# F407.net
KiCad netlist of a schematic drawn in Altium Designer
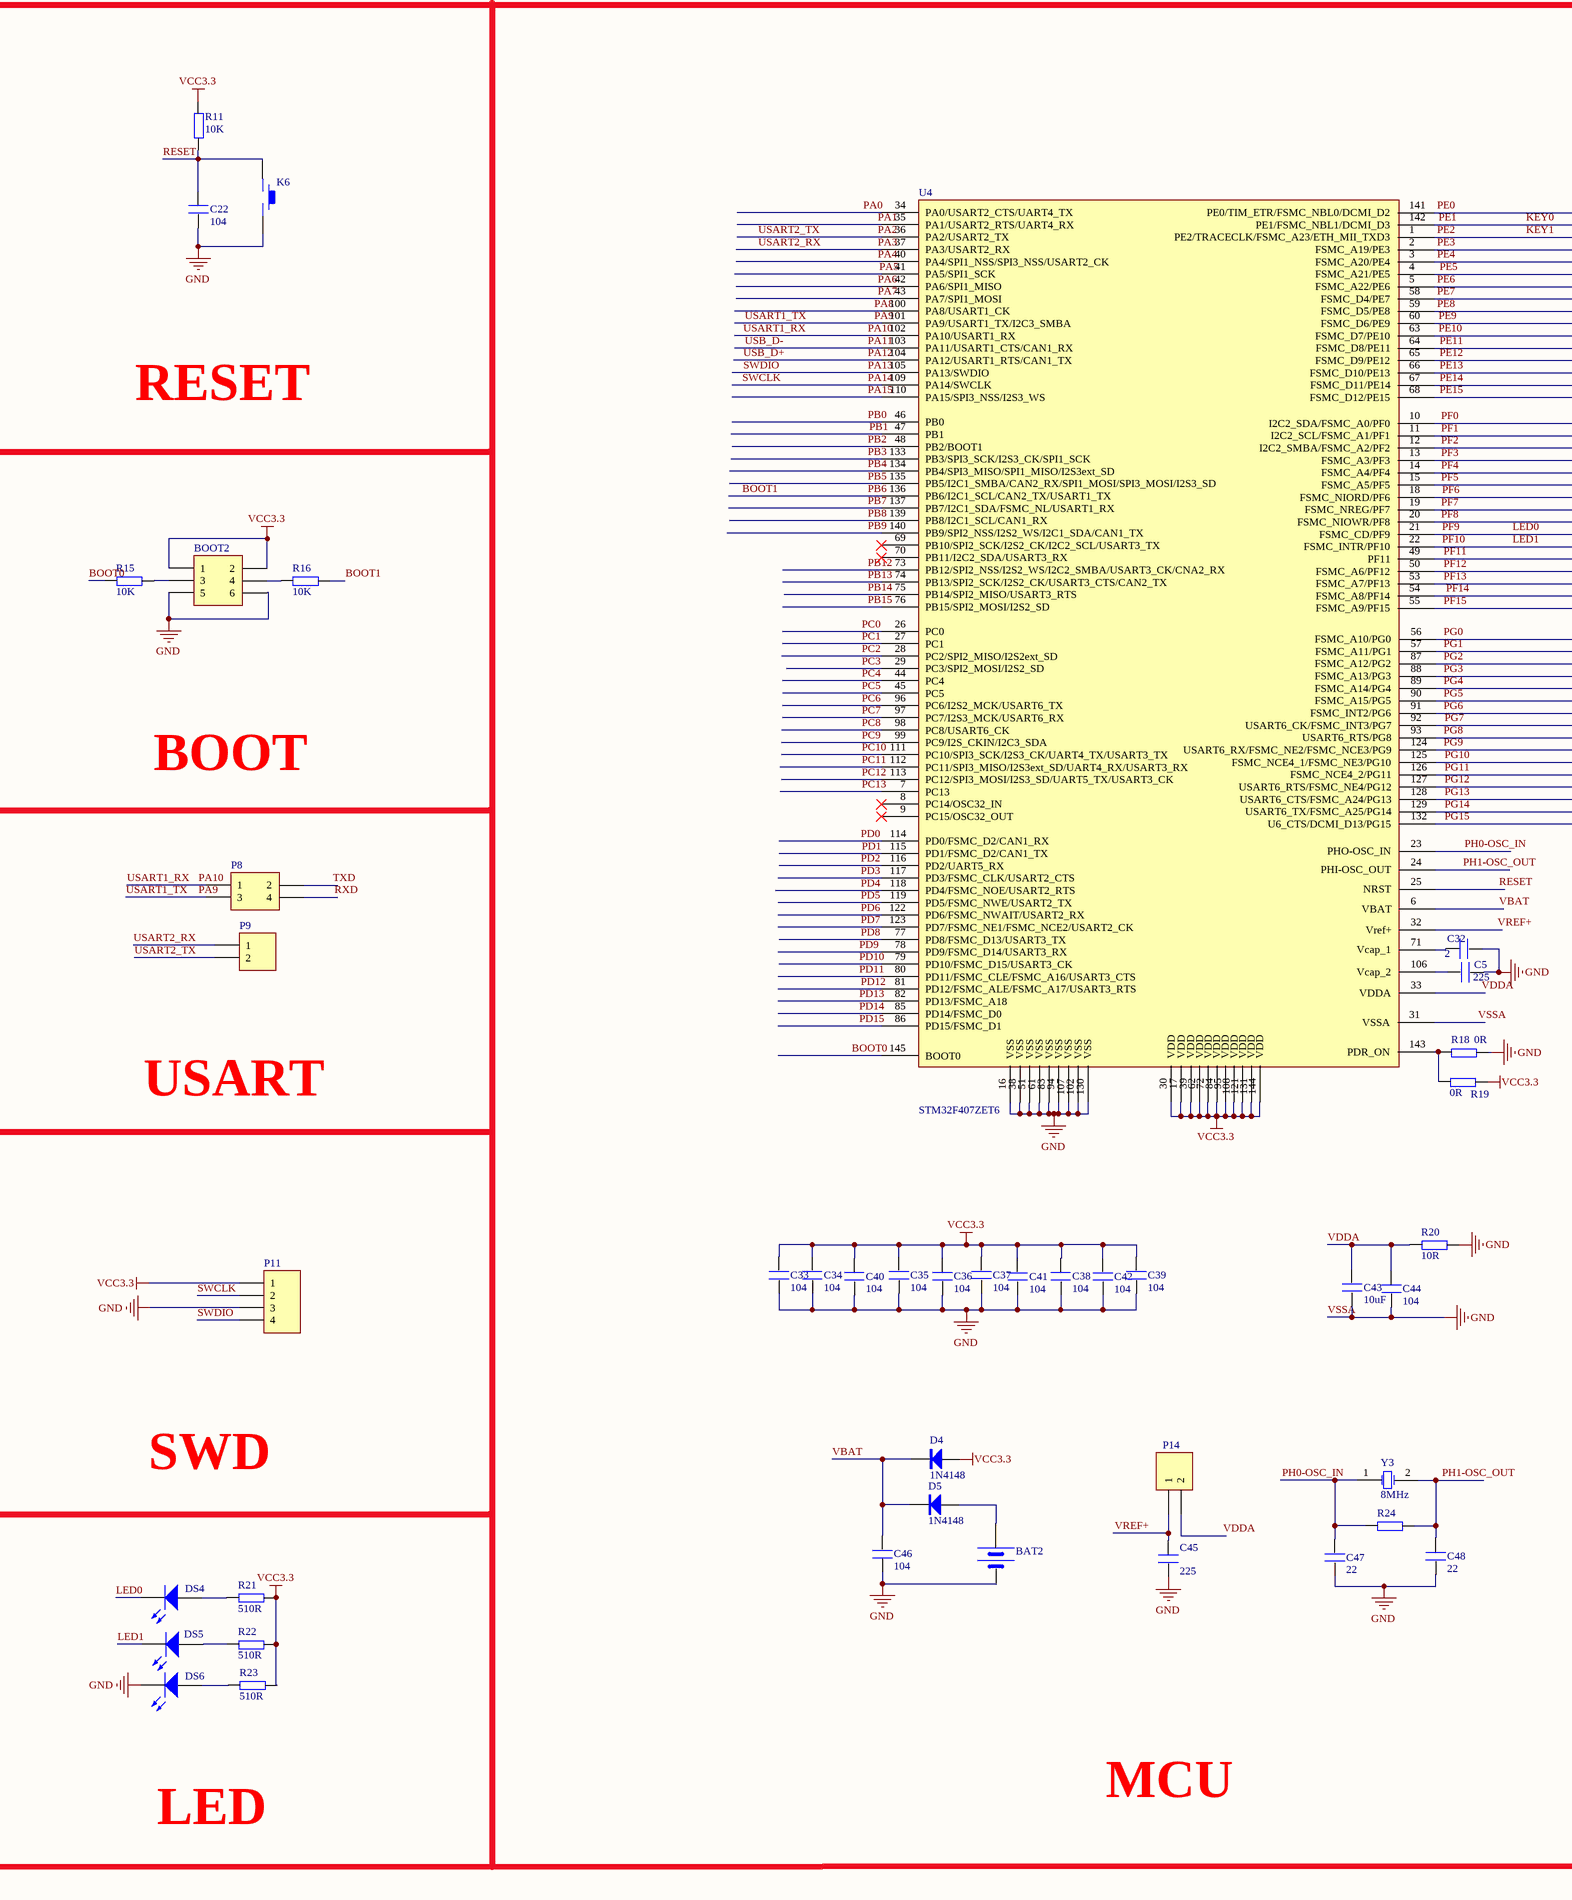
[diagram p0: F407.SchDoc, left]
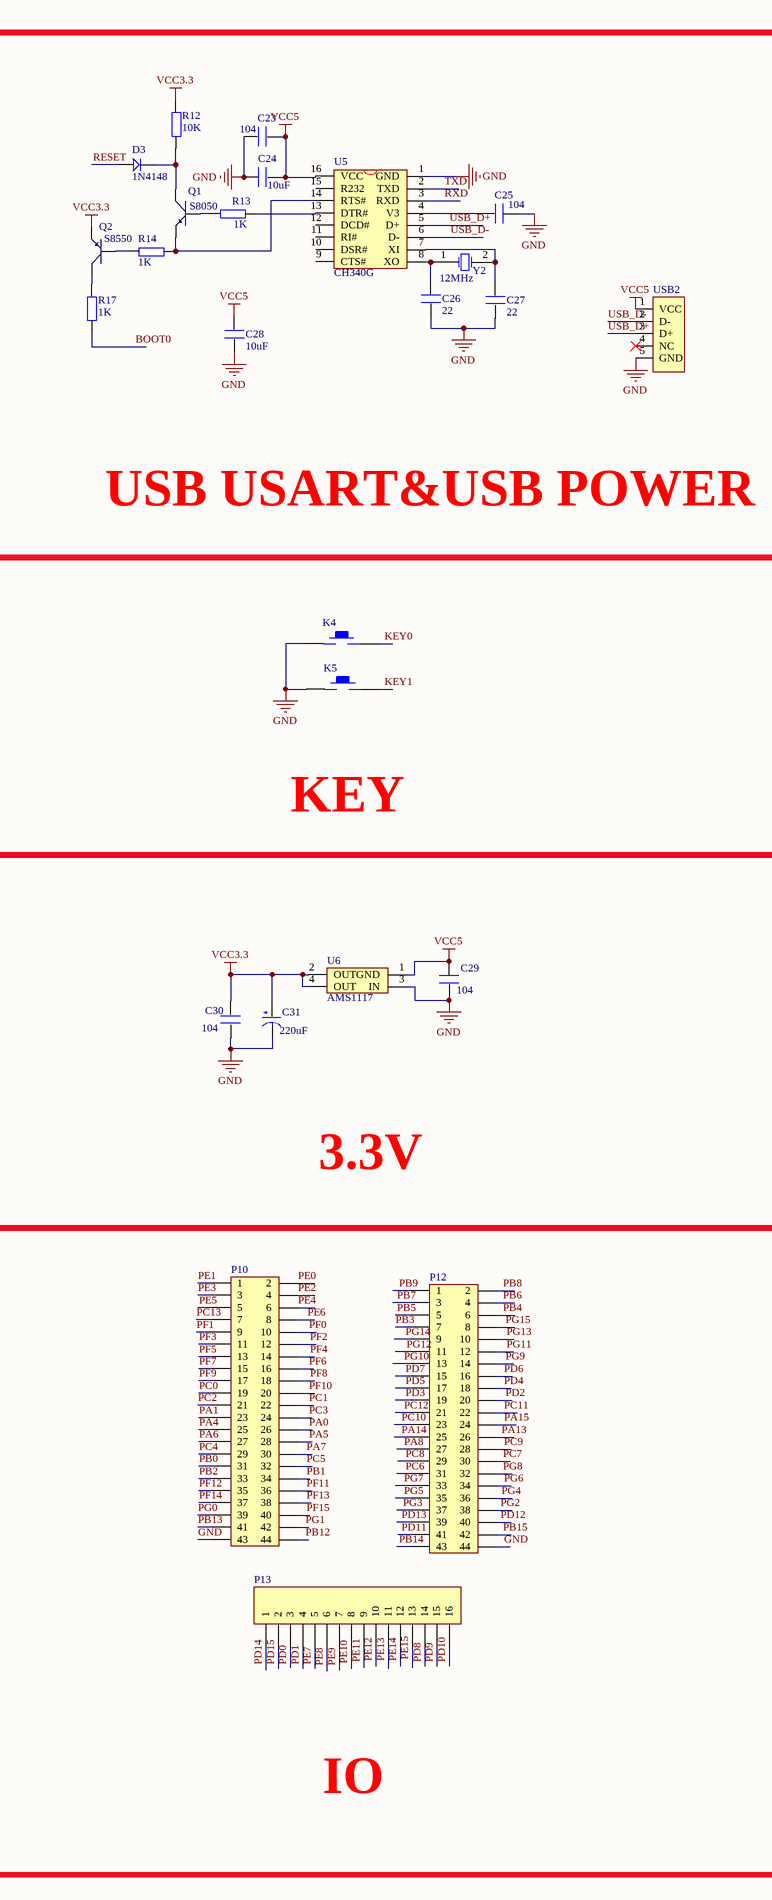
[diagram p1: F407.SchDoc, right]

(export (version "E")
  (design (tool "Eeschema 10.0.6"))
  (components
    (comp (ref "2")
      (value "225")
      (footprint "0603P")
      (libsource (lib "Explorer STM32F407封装库_SCH") (part "C"))
    )
    (comp (ref "BAT2")
      (value "BAT")
      (footprint "BATM")
      (libsource (lib "Explorer STM32F407封装库_SCH") (part "BAT"))
    )
    (comp (ref "BOOT2")
      (value "Header 3X2")
      (footprint "HDR2X3")
      (description "Header, 3-Pin, Dual row")
      (fields (field (name "PUBLISHER") "*"))
      (libsource (lib "Explorer STM32F407封装库_SCH") (part "Header 3X2"))
    )
    (comp (ref "C22")
      (value "104")
      (footprint "0603P")
      (libsource (lib "Explorer STM32F407封装库_SCH") (part "C"))
    )
    (comp (ref "C23")
      (value "104")
      (footprint "0603P")
      (libsource (lib "Explorer STM32F407封装库_SCH") (part "C"))
    )
    (comp (ref "C24")
      (value "10uF")
      (footprint "0603P")
      (libsource (lib "Explorer STM32F407封装库_SCH") (part "C"))
    )
    (comp (ref "C25")
      (value "104")
      (footprint "0603P")
      (libsource (lib "Explorer STM32F407封装库_SCH") (part "C"))
    )
    (comp (ref "C26")
      (value "22")
      (footprint "0603P")
      (libsource (lib "Explorer STM32F407封装库_SCH") (part "C"))
    )
    (comp (ref "C27")
      (value "22")
      (footprint "0603P")
      (libsource (lib "Explorer STM32F407封装库_SCH") (part "C"))
    )
    (comp (ref "C28")
      (value "10uF")
      (footprint "0603P")
      (libsource (lib "Explorer STM32F407封装库_SCH") (part "C"))
    )
    (comp (ref "C29")
      (value "104")
      (footprint "0603P")
      (libsource (lib "Explorer STM32F407封装库_SCH") (part "C"))
    )
    (comp (ref "C30")
      (value "104")
      (footprint "0603P")
      (libsource (lib "Explorer STM32F407封装库_SCH") (part "C"))
    )
    (comp (ref "C31")
      (value "220uF")
      (footprint "C1206")
      (libsource (lib "Explorer STM32F407封装库_SCH") (part "CAP"))
    )
    (comp (ref "C32")
      (value "C5")
      (footprint "0603P")
      (libsource (lib "Explorer STM32F407封装库_SCH") (part "C"))
    )
    (comp (ref "C33")
      (value "104")
      (footprint "0603P")
      (libsource (lib "Explorer STM32F407封装库_SCH") (part "C"))
    )
    (comp (ref "C34")
      (value "104")
      (footprint "0603P")
      (libsource (lib "Explorer STM32F407封装库_SCH") (part "C"))
    )
    (comp (ref "C35")
      (value "104")
      (footprint "0603P")
      (libsource (lib "Explorer STM32F407封装库_SCH") (part "C"))
    )
    (comp (ref "C36")
      (value "104")
      (footprint "0603P")
      (libsource (lib "Explorer STM32F407封装库_SCH") (part "C"))
    )
    (comp (ref "C37")
      (value "104")
      (footprint "0603P")
      (libsource (lib "Explorer STM32F407封装库_SCH") (part "C"))
    )
    (comp (ref "C38")
      (value "104")
      (footprint "0603P")
      (libsource (lib "Explorer STM32F407封装库_SCH") (part "C"))
    )
    (comp (ref "C39")
      (value "104")
      (footprint "0603P")
      (libsource (lib "Explorer STM32F407封装库_SCH") (part "C"))
    )
    (comp (ref "C40")
      (value "104")
      (footprint "0603P")
      (libsource (lib "Explorer STM32F407封装库_SCH") (part "C"))
    )
    (comp (ref "C41")
      (value "104")
      (footprint "0603P")
      (libsource (lib "Explorer STM32F407封装库_SCH") (part "C"))
    )
    (comp (ref "C42")
      (value "104")
      (footprint "0603P")
      (libsource (lib "Explorer STM32F407封装库_SCH") (part "C"))
    )
    (comp (ref "C43")
      (value "10uF")
      (footprint "0603P")
      (libsource (lib "Explorer STM32F407封装库_SCH") (part "C"))
    )
    (comp (ref "C44")
      (value "104")
      (footprint "0603P")
      (libsource (lib "Explorer STM32F407封装库_SCH") (part "C"))
    )
    (comp (ref "C45")
      (value "225")
      (footprint "0603P")
      (libsource (lib "Explorer STM32F407封装库_SCH") (part "C"))
    )
    (comp (ref "C46")
      (value "104")
      (footprint "0603P")
      (libsource (lib "Explorer STM32F407封装库_SCH") (part "C"))
    )
    (comp (ref "C47")
      (value "22")
      (footprint "0603P")
      (libsource (lib "Explorer STM32F407封装库_SCH") (part "C"))
    )
    (comp (ref "C48")
      (value "22")
      (footprint "0603P")
      (libsource (lib "Explorer STM32F407封装库_SCH") (part "C"))
    )
    (comp (ref "D3")
      (value "1N4148")
      (footprint "SOD-123")
      (libsource (lib "Explorer STM32F407封装库_SCH") (part "D"))
    )
    (comp (ref "D4")
      (value "1N4148")
      (footprint "MINI_MELF (LL34)")
      (description "高速开关二极管")
      (fields (field (name "版权归属") "源创客"))
      (libsource (lib "8.1   - 二极管-整流桥") (part "1N4148"))
    )
    (comp (ref "D5")
      (value "1N4148")
      (footprint "MINI_MELF (LL34)")
      (description "高速开关二极管")
      (fields (field (name "版权归属") "源创客"))
      (libsource (lib "8.1   - 二极管-整流桥") (part "1N4148"))
    )
    (comp (ref "DS4")
      (value "LED0")
      (footprint "SMDLED")
      (description "Typical RED, GREEN, YELLOW, AMBER GaAs LED")
      (fields (field (name "PUBLISHER") "*"))
      (libsource (lib "Explorer STM32F407封装库_SCH") (part "LED2"))
    )
    (comp (ref "DS5")
      (value "LED1")
      (footprint "SMDLED")
      (description "Typical RED, GREEN, YELLOW, AMBER GaAs LED")
      (fields (field (name "PUBLISHER") "*"))
      (libsource (lib "Explorer STM32F407封装库_SCH") (part "LED2"))
    )
    (comp (ref "DS6")
      (value "LED3")
      (footprint "SMDLED")
      (description "Typical RED, GREEN, YELLOW, AMBER GaAs LED")
      (fields (field (name "PUBLISHER") "*"))
      (libsource (lib "Explorer STM32F407封装库_SCH") (part "LED2"))
    )
    (comp (ref "K4")
      (value "KEY_M")
      (footprint "KEY_M")
      (libsource (lib "Explorer STM32F407封装库_SCH") (part "KEY_M"))
    )
    (comp (ref "K5")
      (value "KEY_M")
      (footprint "KEY_M")
      (libsource (lib "Explorer STM32F407封装库_SCH") (part "KEY_M"))
    )
    (comp (ref "K6") (value "~") (footprint "KEY_M") (libsource (lib "") (part "KEY_M_1")))
    (comp (ref "P8")
      (value "Header 2X2")
      (footprint "HDR2X2")
      (description "Header, 2-Pin, Dual row")
      (fields (field (name "PUBLISHER") "*"))
      (libsource (lib "Explorer STM32F407封装库_SCH") (part "Header 2X2"))
    )
    (comp (ref "P9")
      (value "Header 2")
      (footprint "HDR1X2")
      (description "Header, 2-Pin")
      (fields (field (name "PUBLISHER") "*"))
      (libsource (lib "") (part "Header 2_1"))
    )
    (comp (ref "P10")
      (value "HEAD2*22")
      (footprint "HEAD2*22")
      (libsource (lib "Explorer STM32F407封装库_SCH") (part "HEAD2*22"))
    )
    (comp (ref "P11")
      (value "Header 4")
      (footprint "HDR1X4")
      (description "Header, 4-Pin")
      (fields (field (name "PUBLISHER") "*"))
      (libsource (lib "Explorer STM32F407封装库_SCH") (part "Header 4"))
    )
    (comp (ref "P12")
      (value "HEAD2*22")
      (footprint "HEAD2*22")
      (libsource (lib "Explorer STM32F407封装库_SCH") (part "HEAD2*22"))
    )
    (comp (ref "P13")
      (value "Header 16")
      (footprint "HDR1X16")
      (description "Header, 16-Pin")
      (fields (field (name "PUBLISHER") "*"))
      (libsource (lib "Explorer STM32F407封装库_SCH") (part "Header 16"))
    )
    (comp (ref "P14")
      (value "~")
      (footprint "HDR1X2")
      (description "Header, 2-Pin")
      (fields (field (name "PUBLISHER") "*"))
      (libsource (lib "Explorer STM32F407封装库_SCH") (part "Header 2"))
    )
    (comp (ref "Q1")
      (value "S8050")
      (footprint "SOT-23R")
      (description "8050/BCW846/BCW847")
      (libsource (lib "Explorer STM32F407封装库_SCH") (part "NPN"))
    )
    (comp (ref "Q2")
      (value "S8550")
      (footprint "SOT-23R")
      (description "8550/BCW68")
      (libsource (lib "Explorer STM32F407封装库_SCH") (part "PNP"))
    )
    (comp (ref "R11")
      (value "10K")
      (footprint "0805")
      (libsource (lib "Explorer STM32F407封装库_SCH") (part "R"))
    )
    (comp (ref "R12")
      (value "10K")
      (footprint "0805")
      (libsource (lib "Explorer STM32F407封装库_SCH") (part "R"))
    )
    (comp (ref "R13")
      (value "1K")
      (footprint "0805")
      (libsource (lib "Explorer STM32F407封装库_SCH") (part "R"))
    )
    (comp (ref "R14")
      (value "1K")
      (footprint "0805")
      (libsource (lib "Explorer STM32F407封装库_SCH") (part "R"))
    )
    (comp (ref "R15")
      (value "10K")
      (footprint "0805")
      (libsource (lib "Explorer STM32F407封装库_SCH") (part "R"))
    )
    (comp (ref "R16")
      (value "10K")
      (footprint "0805")
      (libsource (lib "Explorer STM32F407封装库_SCH") (part "R"))
    )
    (comp (ref "R17")
      (value "1K")
      (footprint "0805")
      (libsource (lib "Explorer STM32F407封装库_SCH") (part "R"))
    )
    (comp (ref "R18")
      (value "0R")
      (footprint "0805")
      (libsource (lib "Explorer STM32F407封装库_SCH") (part "R"))
    )
    (comp (ref "R19")
      (value "0R")
      (footprint "0805")
      (libsource (lib "Explorer STM32F407封装库_SCH") (part "R"))
    )
    (comp (ref "R20")
      (value "10R")
      (footprint "0805")
      (libsource (lib "Explorer STM32F407封装库_SCH") (part "R"))
    )
    (comp (ref "R21")
      (value "510R")
      (footprint "0805")
      (libsource (lib "Explorer STM32F407封装库_SCH") (part "R"))
    )
    (comp (ref "R22")
      (value "510R")
      (footprint "0805")
      (libsource (lib "Explorer STM32F407封装库_SCH") (part "R"))
    )
    (comp (ref "R23")
      (value "510R")
      (footprint "0805")
      (libsource (lib "Explorer STM32F407封装库_SCH") (part "R"))
    )
    (comp (ref "R24") (value "R") (footprint "0805") (libsource (lib "Explorer STM32F407封装库_SCH") (part "R")))
    (comp (ref "U4")
      (value "STM32F407ZET6")
      (footprint "LQFP144")
      (libsource (lib "PCB_Project") (part "STM32F407ZET6"))
    )
    (comp (ref "U5")
      (value "CH340G")
      (footprint "SOP16M")
      (description "USB2UART")
      (libsource (lib "Explorer STM32F407封装库_SCH") (part "CH340G"))
    )
    (comp (ref "U6")
      (value "AMS1117")
      (footprint "AMS1117")
      (libsource (lib "Explorer STM32F407封装库_SCH") (part "AMS1117"))
    )
    (comp (ref "USB2")
      (value "USB5")
      (footprint "USB/SM0.8-6H5")
      (libsource (lib "Explorer STM32F407封装库_SCH") (part "USB5"))
    )
    (comp (ref "Y2")
      (value "12MHz")
      (footprint "XTAL_US")
      (description "Crystal Oscillator")
      (fields (field (name "PUBLISHER") "*"))
      (libsource (lib "Explorer STM32F407封装库_SCH") (part "XTAL"))
    )
    (comp (ref "Y3")
      (value "8MHz")
      (footprint "XTAL_US")
      (description "Crystal Oscillator")
      (fields (field (name "PUBLISHER") "*"))
      (libsource (lib "Explorer STM32F407封装库_SCH") (part "XTAL"))
    )
  )
  (nets
    (net (code "1") (name "/BOOT0") (class "Default")
      (node (ref "R15") (pin "1") (pintype "passive"))
      (node (ref "R17") (pin "1") (pintype "passive"))
      (node (ref "U4") (pin "145") (pinfunction "BOOT0_145") (pintype "passive"))
    )
    (net (code "2") (name "/BOOT1") (class "Default")
      (node (ref "P12") (pin "4") (pinfunction "4_4") (pintype "passive"))
      (node (ref "R16") (pin "2") (pintype "passive"))
      (node (ref "U4") (pin "136") (pinfunction "PB6/I2C1_SCL/CAN2_TX/USART1_TX_136") (pintype "passive"))
    )
    (net (code "3") (name "/KEY0") (class "Default")
      (node (ref "K4") (pin "2") (pinfunction "2_2") (pintype "passive"))
      (node (ref "P10") (pin "1") (pinfunction "1_1") (pintype "passive"))
      (node (ref "U4") (pin "142") (pinfunction "PE1/FSMC_NBL1/DCMI_D3_142") (pintype "passive"))
    )
    (net (code "4") (name "/KEY1") (class "Default")
      (node (ref "K5") (pin "2") (pinfunction "2_2") (pintype "passive"))
      (node (ref "P10") (pin "4") (pinfunction "4_4") (pintype "passive"))
      (node (ref "U4") (pin "1") (pinfunction "PE2/TRACECLK/FSMC_A23/ETH_MII_TXD3_1") (pintype "passive"))
    )
    (net (code "5") (name "/LED0") (class "Default")
      (node (ref "DS4") (pin "2") (pinfunction "K_2") (pintype "passive"))
      (node (ref "P10") (pin "17") (pinfunction "17_17") (pintype "passive"))
      (node (ref "U4") (pin "21") (pinfunction "FSMC_CD/PF9_21") (pintype "passive"))
    )
    (net (code "6") (name "/LED1") (class "Default")
      (node (ref "DS5") (pin "2") (pinfunction "K_2") (pintype "passive"))
      (node (ref "P10") (pin "20") (pinfunction "20_20") (pintype "passive"))
      (node (ref "U4") (pin "22") (pinfunction "FSMC_INTR/PF10_22") (pintype "passive"))
    )
    (net (code "7") (name "/PA0") (class "Default")
      (node (ref "P10") (pin "26") (pinfunction "26_26") (pintype "passive"))
      (node (ref "U4") (pin "34") (pinfunction "PA0/USART2_CTS/UART4_TX_34") (pintype "passive"))
    )
    (net (code "8") (name "/PA1") (class "Default")
      (node (ref "P10") (pin "23") (pinfunction "23_23") (pintype "passive"))
      (node (ref "U4") (pin "35") (pinfunction "PA1/USART2_RTS/UART4_RX_35") (pintype "passive"))
    )
    (net (code "9") (name "/PA2") (class "Default")
      (node (ref "P9") (pin "2") (pinfunction "2_2") (pintype "passive"))
      (node (ref "U4") (pin "36") (pinfunction "PA2/USART2_TX_36") (pintype "passive"))
    )
    (net (code "10") (name "/PA3") (class "Default")
      (node (ref "P9") (pin "1") (pinfunction "1_1") (pintype "passive"))
      (node (ref "U4") (pin "37") (pinfunction "PA3/USART2_RX_37") (pintype "passive"))
    )
    (net (code "11") (name "/PA4") (class "Default")
      (node (ref "P10") (pin "25") (pinfunction "25_25") (pintype "passive"))
      (node (ref "U4") (pin "40") (pinfunction "PA4/SPI1_NSS/SPI3_NSS/USART2_CK_40") (pintype "passive"))
    )
    (net (code "12") (name "/PA5") (class "Default")
      (node (ref "P10") (pin "28") (pinfunction "28_28") (pintype "passive"))
      (node (ref "U4") (pin "41") (pinfunction "PA5/SPI1_SCK_41") (pintype "passive"))
    )
    (net (code "13") (name "/PA6") (class "Default")
      (node (ref "P10") (pin "27") (pinfunction "27_27") (pintype "passive"))
      (node (ref "U4") (pin "42") (pinfunction "PA6/SPI1_MISO_42") (pintype "passive"))
    )
    (net (code "14") (name "/PA7") (class "Default")
      (node (ref "P10") (pin "30") (pinfunction "30_30") (pintype "passive"))
      (node (ref "U4") (pin "43") (pinfunction "PA7/SPI1_MOSI_43") (pintype "passive"))
    )
    (net (code "15") (name "/PA8") (class "Default")
      (node (ref "P12") (pin "27") (pinfunction "27_27") (pintype "passive"))
      (node (ref "U4") (pin "100") (pinfunction "PA8/USART1_CK_100") (pintype "passive"))
    )
    (net (code "16") (name "/PA9") (class "Default")
      (node (ref "P8") (pin "3") (pinfunction "3_3") (pintype "passive"))
      (node (ref "U4") (pin "101") (pinfunction "PA9/USART1_TX/I2C3_SMBA_101") (pintype "passive"))
    )
    (net (code "17") (name "/PA10") (class "Default")
      (node (ref "P8") (pin "1") (pinfunction "1_1") (pintype "passive"))
      (node (ref "U4") (pin "102") (pinfunction "PA10/USART1_RX_102") (pintype "passive"))
    )
    (net (code "18") (name "/PA11") (class "Default")
      (node (ref "U4") (pin "103") (pinfunction "PA11/USART1_CTS/CAN1_RX_103") (pintype "passive"))
      (node (ref "U5") (pin "6") (pinfunction "D-_6") (pintype "passive"))
      (node (ref "USB2") (pin "2") (pinfunction "D-_2") (pintype "passive"))
    )
    (net (code "19") (name "/PA12") (class "Default")
      (node (ref "U4") (pin "104") (pinfunction "PA12/USART1_RTS/CAN1_TX_104") (pintype "passive"))
      (node (ref "U5") (pin "5") (pinfunction "D+_5") (pintype "passive"))
      (node (ref "USB2") (pin "3") (pinfunction "D+_3") (pintype "passive"))
    )
    (net (code "20") (name "/PA13") (class "Default")
      (node (ref "P11") (pin "4") (pinfunction "4_4") (pintype "passive"))
      (node (ref "P12") (pin "26") (pinfunction "26_26") (pintype "passive"))
      (node (ref "U4") (pin "105") (pinfunction "PA13/SWDIO_105") (pintype "passive"))
    )
    (net (code "21") (name "/PA14") (class "Default")
      (node (ref "P11") (pin "2") (pinfunction "2_2") (pintype "passive"))
      (node (ref "P12") (pin "25") (pinfunction "25_25") (pintype "passive"))
      (node (ref "U4") (pin "109") (pinfunction "PA14/SWCLK_109") (pintype "passive"))
    )
    (net (code "22") (name "/PA15") (class "Default")
      (node (ref "P12") (pin "24") (pinfunction "24_24") (pintype "passive"))
      (node (ref "U4") (pin "110") (pinfunction "PA15/SPI3_NSS/I2S3_WS_110") (pintype "passive"))
    )
    (net (code "23") (name "/PB0") (class "Default")
      (node (ref "P10") (pin "31") (pinfunction "31_31") (pintype "passive"))
      (node (ref "U4") (pin "46") (pinfunction "PB0_46") (pintype "passive"))
    )
    (net (code "24") (name "/PB1") (class "Default")
      (node (ref "P10") (pin "34") (pinfunction "34_34") (pintype "passive"))
      (node (ref "U4") (pin "47") (pinfunction "PB1_47") (pintype "passive"))
    )
    (net (code "25") (name "/PB2") (class "Default")
      (node (ref "P10") (pin "33") (pinfunction "33_33") (pintype "passive"))
      (node (ref "U4") (pin "48") (pinfunction "PB2/BOOT1_48") (pintype "passive"))
    )
    (net (code "26") (name "/PB3") (class "Default")
      (node (ref "P12") (pin "7") (pinfunction "7_7") (pintype "passive"))
      (node (ref "U4") (pin "133") (pinfunction "PB3/SPI3_SCK/I2S3_CK/SPI1_SCK_133") (pintype "passive"))
    )
    (net (code "27") (name "/PB4") (class "Default")
      (node (ref "P12") (pin "6") (pinfunction "6_6") (pintype "passive"))
      (node (ref "U4") (pin "134") (pinfunction "PB4/SPI3_MISO/SPI1_MISO/I2S3ext_SD_134") (pintype "passive"))
    )
    (net (code "28") (name "/PB5") (class "Default")
      (node (ref "P12") (pin "5") (pinfunction "5_5") (pintype "passive"))
      (node (ref "U4") (pin "135") (pinfunction "PB5/I2C1_SMBA/CAN2_RX/SPI1_MOSI/SPI3_MOSI/I2S3_SD_135") (pintype "passive"))
    )
    (net (code "29") (name "/PB7") (class "Default")
      (node (ref "P12") (pin "3") (pinfunction "3_3") (pintype "passive"))
      (node (ref "U4") (pin "137") (pinfunction "PB7/I2C1_SDA/FSMC_NL/USART1_RX_137") (pintype "passive"))
    )
    (net (code "30") (name "/PB8") (class "Default")
      (node (ref "P12") (pin "2") (pinfunction "2_2") (pintype "passive"))
      (node (ref "U4") (pin "139") (pinfunction "PB8/I2C1_SCL/CAN1_RX_139") (pintype "passive"))
    )
    (net (code "31") (name "/PB9") (class "Default")
      (node (ref "P12") (pin "1") (pinfunction "1_1") (pintype "passive"))
      (node (ref "U4") (pin "140") (pinfunction "PB9/SPI2_NSS/I2S2_WS/I2C1_SDA/CAN1_TX_140") (pintype "passive"))
    )
    (net (code "32") (name "/PB12") (class "Default")
      (node (ref "P10") (pin "44") (pinfunction "44_44") (pintype "passive"))
      (node (ref "U4") (pin "73") (pinfunction "PB12/SPI2_NSS/I2S2_WS/I2C2_SMBA/USART3_CK/CNA2_RX_73") (pintype "passive"))
    )
    (net (code "33") (name "/PB13") (class "Default")
      (node (ref "P10") (pin "41") (pinfunction "41_41") (pintype "passive"))
      (node (ref "U4") (pin "74") (pinfunction "PB13/SPI2_SCK/I2S2_CK/USART3_CTS/CAN2_TX_74") (pintype "passive"))
    )
    (net (code "34") (name "/PB14") (class "Default")
      (node (ref "P12") (pin "43") (pinfunction "43_43") (pintype "passive"))
      (node (ref "U4") (pin "75") (pinfunction "PB14/SPI2_MISO/USART3_RTS_75") (pintype "passive"))
    )
    (net (code "35") (name "/PB15") (class "Default")
      (node (ref "P12") (pin "42") (pinfunction "42_42") (pintype "passive"))
      (node (ref "U4") (pin "76") (pinfunction "PB15/SPI2_MOSI/I2S2_SD_76") (pintype "passive"))
    )
    (net (code "36") (name "/PC0") (class "Default")
      (node (ref "P10") (pin "19") (pinfunction "19_19") (pintype "passive"))
      (node (ref "U4") (pin "26") (pinfunction "PC0_26") (pintype "passive"))
    )
    (net (code "37") (name "/PC1") (class "Default")
      (node (ref "P10") (pin "22") (pinfunction "22_22") (pintype "passive"))
      (node (ref "U4") (pin "27") (pinfunction "PC1_27") (pintype "passive"))
    )
    (net (code "38") (name "/PC2") (class "Default")
      (node (ref "P10") (pin "21") (pinfunction "21_21") (pintype "passive"))
      (node (ref "U4") (pin "28") (pinfunction "PC2/SPI2_MISO/I2S2ext_SD_28") (pintype "passive"))
    )
    (net (code "39") (name "/PC3") (class "Default")
      (node (ref "P10") (pin "24") (pinfunction "24_24") (pintype "passive"))
      (node (ref "U4") (pin "29") (pinfunction "PC3/SPI2_MOSI/I2S2_SD_29") (pintype "passive"))
    )
    (net (code "40") (name "/PC4") (class "Default")
      (node (ref "P10") (pin "29") (pinfunction "29_29") (pintype "passive"))
      (node (ref "U4") (pin "44") (pinfunction "PC4_44") (pintype "passive"))
    )
    (net (code "41") (name "/PC5") (class "Default")
      (node (ref "P10") (pin "32") (pinfunction "32_32") (pintype "passive"))
      (node (ref "U4") (pin "45") (pinfunction "PC5_45") (pintype "passive"))
    )
    (net (code "42") (name "/PC6") (class "Default")
      (node (ref "P12") (pin "31") (pinfunction "31_31") (pintype "passive"))
      (node (ref "U4") (pin "96") (pinfunction "PC6/I2S2_MCK/USART6_TX_96") (pintype "passive"))
    )
    (net (code "43") (name "/PC7") (class "Default")
      (node (ref "P12") (pin "30") (pinfunction "30_30") (pintype "passive"))
      (node (ref "U4") (pin "97") (pinfunction "PC7/I2S3_MCK/USART6_RX_97") (pintype "passive"))
    )
    (net (code "44") (name "/PC8") (class "Default")
      (node (ref "P12") (pin "29") (pinfunction "29_29") (pintype "passive"))
      (node (ref "U4") (pin "98") (pinfunction "PC8/USART6_CK_98") (pintype "passive"))
    )
    (net (code "45") (name "/PC9") (class "Default")
      (node (ref "P12") (pin "28") (pinfunction "28_28") (pintype "passive"))
      (node (ref "U4") (pin "99") (pinfunction "PC9/I2S_CKIN/I2C3_SDA_99") (pintype "passive"))
    )
    (net (code "46") (name "/PC10") (class "Default")
      (node (ref "P12") (pin "23") (pinfunction "23_23") (pintype "passive"))
      (node (ref "U4") (pin "111") (pinfunction "PC10/SPI3_SCK/I2S3_CK/UART4_TX/USART3_TX_111") (pintype "passive"))
    )
    (net (code "47") (name "/PC11") (class "Default")
      (node (ref "P12") (pin "22") (pinfunction "22_22") (pintype "passive"))
      (node (ref "U4") (pin "112") (pinfunction "PC11/SPI3_MISO/I2S3ext_SD/UART4_RX/USART3_RX_112") (pintype "passive"))
    )
    (net (code "48") (name "/PC12") (class "Default")
      (node (ref "P12") (pin "21") (pinfunction "21_21") (pintype "passive"))
      (node (ref "U4") (pin "113") (pinfunction "PC12/SPI3_MOSI/I2S3_SD/UART5_TX/USART3_CK_113") (pintype "passive"))
    )
    (net (code "49") (name "/PC13") (class "Default")
      (node (ref "P10") (pin "7") (pinfunction "7_7") (pintype "passive"))
      (node (ref "U4") (pin "7") (pinfunction "PC13_7") (pintype "passive"))
    )
    (net (code "50") (name "/PD0") (class "Default")
      (node (ref "P13") (pin "3") (pinfunction "3_3") (pintype "passive"))
      (node (ref "U4") (pin "114") (pinfunction "PD0/FSMC_D2/CAN1_RX_114") (pintype "passive"))
    )
    (net (code "51") (name "/PD1") (class "Default")
      (node (ref "P13") (pin "4") (pinfunction "4_4") (pintype "passive"))
      (node (ref "U4") (pin "115") (pinfunction "PD1/FSMC_D2/CAN1_TX_115") (pintype "passive"))
    )
    (net (code "52") (name "/PD2") (class "Default")
      (node (ref "P12") (pin "20") (pinfunction "20_20") (pintype "passive"))
      (node (ref "U4") (pin "116") (pinfunction "PD2/UART5_RX_116") (pintype "passive"))
    )
    (net (code "53") (name "/PD3") (class "Default")
      (node (ref "P12") (pin "19") (pinfunction "19_19") (pintype "passive"))
      (node (ref "U4") (pin "117") (pinfunction "PD3/FSMC_CLK/USART2_CTS_117") (pintype "passive"))
    )
    (net (code "54") (name "/PD4") (class "Default")
      (node (ref "P12") (pin "18") (pinfunction "18_18") (pintype "passive"))
      (node (ref "U4") (pin "118") (pinfunction "PD4/FSMC_NOE/USART2_RTS_118") (pintype "passive"))
    )
    (net (code "55") (name "/PD5") (class "Default")
      (node (ref "P12") (pin "17") (pinfunction "17_17") (pintype "passive"))
      (node (ref "U4") (pin "119") (pinfunction "PD5/FSMC_NWE/USART2_TX_119") (pintype "passive"))
    )
    (net (code "56") (name "/PD6") (class "Default")
      (node (ref "P12") (pin "16") (pinfunction "16_16") (pintype "passive"))
      (node (ref "U4") (pin "122") (pinfunction "PD6/FSMC_NWAIT/USART2_RX_122") (pintype "passive"))
    )
    (net (code "57") (name "/PD7") (class "Default")
      (node (ref "P12") (pin "15") (pinfunction "15_15") (pintype "passive"))
      (node (ref "U4") (pin "123") (pinfunction "PD7/FSMC_NE1/FSMC_NCE2/USART2_CK_123") (pintype "passive"))
    )
    (net (code "58") (name "/PD8") (class "Default")
      (node (ref "P13") (pin "14") (pinfunction "14_14") (pintype "passive"))
      (node (ref "U4") (pin "77") (pinfunction "PD8/FSMC_D13/USART3_TX_77") (pintype "passive"))
    )
    (net (code "59") (name "/PD9") (class "Default")
      (node (ref "P13") (pin "15") (pinfunction "15_15") (pintype "passive"))
      (node (ref "U4") (pin "78") (pinfunction "PD9/FSMC_D14/USART3_RX_78") (pintype "passive"))
    )
    (net (code "60") (name "/PD10") (class "Default")
      (node (ref "P13") (pin "16") (pinfunction "16_16") (pintype "passive"))
      (node (ref "U4") (pin "79") (pinfunction "PD10/FSMC_D15/USART3_CK_79") (pintype "passive"))
    )
    (net (code "61") (name "/PD11") (class "Default")
      (node (ref "P12") (pin "41") (pinfunction "41_41") (pintype "passive"))
      (node (ref "U4") (pin "80") (pinfunction "PD11/FSMC_CLE/FSMC_A16/USART3_CTS_80") (pintype "passive"))
    )
    (net (code "62") (name "/PD12") (class "Default")
      (node (ref "P12") (pin "40") (pinfunction "40_40") (pintype "passive"))
      (node (ref "U4") (pin "81") (pinfunction "PD12/FSMC_ALE/FSMC_A17/USART3_RTS_81") (pintype "passive"))
    )
    (net (code "63") (name "/PD13") (class "Default")
      (node (ref "P12") (pin "39") (pinfunction "39_39") (pintype "passive"))
      (node (ref "U4") (pin "82") (pinfunction "PD13/FSMC_A18_82") (pintype "passive"))
    )
    (net (code "64") (name "/PD14") (class "Default")
      (node (ref "P13") (pin "1") (pinfunction "1_1") (pintype "passive"))
      (node (ref "U4") (pin "85") (pinfunction "PD14/FSMC_D0_85") (pintype "passive"))
    )
    (net (code "65") (name "/PD15") (class "Default")
      (node (ref "P13") (pin "2") (pinfunction "2_2") (pintype "passive"))
      (node (ref "U4") (pin "86") (pinfunction "PD15/FSMC_D1_86") (pintype "passive"))
    )
    (net (code "66") (name "/PE0") (class "Default")
      (node (ref "P10") (pin "2") (pinfunction "2_2") (pintype "passive"))
      (node (ref "U4") (pin "141") (pinfunction "PE0/TIM_ETR/FSMC_NBL0/DCMI_D2_141") (pintype "passive"))
    )
    (net (code "67") (name "/PE3") (class "Default")
      (node (ref "P10") (pin "3") (pinfunction "3_3") (pintype "passive"))
      (node (ref "U4") (pin "2") (pinfunction "FSMC_A19/PE3_2") (pintype "passive"))
    )
    (net (code "68") (name "/PE4") (class "Default")
      (node (ref "P10") (pin "6") (pinfunction "6_6") (pintype "passive"))
      (node (ref "U4") (pin "3") (pinfunction "FSMC_A20/PE4_3") (pintype "passive"))
    )
    (net (code "69") (name "/PE5") (class "Default")
      (node (ref "P10") (pin "5") (pinfunction "5_5") (pintype "passive"))
      (node (ref "U4") (pin "4") (pinfunction "FSMC_A21/PE5_4") (pintype "passive"))
    )
    (net (code "70") (name "/PE6") (class "Default")
      (node (ref "P10") (pin "8") (pinfunction "8_8") (pintype "passive"))
      (node (ref "U4") (pin "5") (pinfunction "FSMC_A22/PE6_5") (pintype "passive"))
    )
    (net (code "71") (name "/PE7") (class "Default")
      (node (ref "P13") (pin "5") (pinfunction "5_5") (pintype "passive"))
      (node (ref "U4") (pin "58") (pinfunction "FSMC_D4/PE7_58") (pintype "passive"))
    )
    (net (code "72") (name "/PE8") (class "Default")
      (node (ref "P13") (pin "6") (pinfunction "6_6") (pintype "passive"))
      (node (ref "U4") (pin "59") (pinfunction "FSMC_D5/PE8_59") (pintype "passive"))
    )
    (net (code "73") (name "/PE9") (class "Default")
      (node (ref "P13") (pin "7") (pinfunction "7_7") (pintype "passive"))
      (node (ref "U4") (pin "60") (pinfunction "FSMC_D6/PE9_60") (pintype "passive"))
    )
    (net (code "74") (name "/PE10") (class "Default")
      (node (ref "P13") (pin "8") (pinfunction "8_8") (pintype "passive"))
      (node (ref "U4") (pin "63") (pinfunction "FSMC_D7/PE10_63") (pintype "passive"))
    )
    (net (code "75") (name "/PE11") (class "Default")
      (node (ref "P13") (pin "9") (pinfunction "9_9") (pintype "passive"))
      (node (ref "U4") (pin "64") (pinfunction "FSMC_D8/PE11_64") (pintype "passive"))
    )
    (net (code "76") (name "/PE12") (class "Default")
      (node (ref "P13") (pin "10") (pinfunction "10_10") (pintype "passive"))
      (node (ref "U4") (pin "65") (pinfunction "FSMC_D9/PE12_65") (pintype "passive"))
    )
    (net (code "77") (name "/PE13") (class "Default")
      (node (ref "P13") (pin "11") (pinfunction "11_11") (pintype "passive"))
      (node (ref "U4") (pin "66") (pinfunction "FSMC_D10/PE13_66") (pintype "passive"))
    )
    (net (code "78") (name "/PE14") (class "Default")
      (node (ref "P13") (pin "12") (pinfunction "12_12") (pintype "passive"))
      (node (ref "U4") (pin "67") (pinfunction "FSMC_D11/PE14_67") (pintype "passive"))
    )
    (net (code "79") (name "/PE15") (class "Default")
      (node (ref "P13") (pin "13") (pinfunction "13_13") (pintype "passive"))
      (node (ref "U4") (pin "68") (pinfunction "FSMC_D12/PE15_68") (pintype "passive"))
    )
    (net (code "80") (name "/PF0") (class "Default")
      (node (ref "P10") (pin "10") (pinfunction "10_10") (pintype "passive"))
      (node (ref "U4") (pin "10") (pinfunction "I2C2_SDA/FSMC_A0/PF0_10") (pintype "passive"))
    )
    (net (code "81") (name "/PF1") (class "Default")
      (node (ref "P10") (pin "9") (pinfunction "9_9") (pintype "passive"))
      (node (ref "U4") (pin "11") (pinfunction "I2C2_SCL/FSMC_A1/PF1_11") (pintype "passive"))
    )
    (net (code "82") (name "/PF2") (class "Default")
      (node (ref "P10") (pin "12") (pinfunction "12_12") (pintype "passive"))
      (node (ref "U4") (pin "12") (pinfunction "I2C2_SMBA/FSMC_A2/PF2_12") (pintype "passive"))
    )
    (net (code "83") (name "/PF3") (class "Default")
      (node (ref "P10") (pin "11") (pinfunction "11_11") (pintype "passive"))
      (node (ref "U4") (pin "13") (pinfunction "FSMC_A3/PF3_13") (pintype "passive"))
    )
    (net (code "84") (name "/PF4") (class "Default")
      (node (ref "P10") (pin "14") (pinfunction "14_14") (pintype "passive"))
      (node (ref "U4") (pin "14") (pinfunction "FSMC_A4/PF4_14") (pintype "passive"))
    )
    (net (code "85") (name "/PF5") (class "Default")
      (node (ref "P10") (pin "13") (pinfunction "13_13") (pintype "passive"))
      (node (ref "U4") (pin "15") (pinfunction "FSMC_A5/PF5_15") (pintype "passive"))
    )
    (net (code "86") (name "/PF6") (class "Default")
      (node (ref "P10") (pin "16") (pinfunction "16_16") (pintype "passive"))
      (node (ref "U4") (pin "18") (pinfunction "FSMC_NIORD/PF6_18") (pintype "passive"))
    )
    (net (code "87") (name "/PF7") (class "Default")
      (node (ref "P10") (pin "15") (pinfunction "15_15") (pintype "passive"))
      (node (ref "U4") (pin "19") (pinfunction "FSMC_NREG/PF7_19") (pintype "passive"))
    )
    (net (code "88") (name "/PF8") (class "Default")
      (node (ref "P10") (pin "18") (pinfunction "18_18") (pintype "passive"))
      (node (ref "U4") (pin "20") (pinfunction "FSMC_NIOWR/PF8_20") (pintype "passive"))
    )
    (net (code "89") (name "/PF11") (class "Default")
      (node (ref "P10") (pin "36") (pinfunction "36_36") (pintype "passive"))
      (node (ref "U4") (pin "49") (pinfunction "PF11_49") (pintype "passive"))
    )
    (net (code "90") (name "/PF12") (class "Default")
      (node (ref "P10") (pin "35") (pinfunction "35_35") (pintype "passive"))
      (node (ref "U4") (pin "50") (pinfunction "FSMC_A6/PF12_50") (pintype "passive"))
    )
    (net (code "91") (name "/PF13") (class "Default")
      (node (ref "P10") (pin "38") (pinfunction "38_38") (pintype "passive"))
      (node (ref "U4") (pin "53") (pinfunction "FSMC_A7/PF13_53") (pintype "passive"))
    )
    (net (code "92") (name "/PF14") (class "Default")
      (node (ref "P10") (pin "37") (pinfunction "37_37") (pintype "passive"))
      (node (ref "U4") (pin "54") (pinfunction "FSMC_A8/PF14_54") (pintype "passive"))
    )
    (net (code "93") (name "/PF15") (class "Default")
      (node (ref "P10") (pin "40") (pinfunction "40_40") (pintype "passive"))
      (node (ref "U4") (pin "55") (pinfunction "FSMC_A9/PF15_55") (pintype "passive"))
    )
    (net (code "94") (name "/PG0") (class "Default")
      (node (ref "P10") (pin "39") (pinfunction "39_39") (pintype "passive"))
      (node (ref "U4") (pin "56") (pinfunction "FSMC_A10/PG0_56") (pintype "passive"))
    )
    (net (code "95") (name "/PG1") (class "Default")
      (node (ref "P10") (pin "42") (pinfunction "42_42") (pintype "passive"))
      (node (ref "U4") (pin "57") (pinfunction "FSMC_A11/PG1_57") (pintype "passive"))
    )
    (net (code "96") (name "/PG2") (class "Default")
      (node (ref "P12") (pin "38") (pinfunction "38_38") (pintype "passive"))
      (node (ref "U4") (pin "87") (pinfunction "FSMC_A12/PG2_87") (pintype "passive"))
    )
    (net (code "97") (name "/PG3") (class "Default")
      (node (ref "P12") (pin "37") (pinfunction "37_37") (pintype "passive"))
      (node (ref "U4") (pin "88") (pinfunction "FSMC_A13/PG3_88") (pintype "passive"))
    )
    (net (code "98") (name "/PG4") (class "Default")
      (node (ref "P12") (pin "36") (pinfunction "36_36") (pintype "passive"))
      (node (ref "U4") (pin "89") (pinfunction "FSMC_A14/PG4_89") (pintype "passive"))
    )
    (net (code "99") (name "/PG5") (class "Default")
      (node (ref "P12") (pin "35") (pinfunction "35_35") (pintype "passive"))
      (node (ref "U4") (pin "90") (pinfunction "FSMC_A15/PG5_90") (pintype "passive"))
    )
    (net (code "100") (name "/PG6") (class "Default")
      (node (ref "P12") (pin "34") (pinfunction "34_34") (pintype "passive"))
      (node (ref "U4") (pin "91") (pinfunction "FSMC_INT2/PG6_91") (pintype "passive"))
    )
    (net (code "101") (name "/PG7") (class "Default")
      (node (ref "P12") (pin "33") (pinfunction "33_33") (pintype "passive"))
      (node (ref "U4") (pin "92") (pinfunction "USART6_CK/FSMC_INT3/PG7_92") (pintype "passive"))
    )
    (net (code "102") (name "/PG8") (class "Default")
      (node (ref "P12") (pin "32") (pinfunction "32_32") (pintype "passive"))
      (node (ref "U4") (pin "93") (pinfunction "USART6_RTS/PG8_93") (pintype "passive"))
    )
    (net (code "103") (name "/PG9") (class "Default")
      (node (ref "P12") (pin "14") (pinfunction "14_14") (pintype "passive"))
      (node (ref "U4") (pin "124") (pinfunction "USART6_RX/FSMC_NE2/FSMC_NCE3/PG9_124") (pintype "passive"))
    )
    (net (code "104") (name "/PG10") (class "Default")
      (node (ref "P12") (pin "13") (pinfunction "13_13") (pintype "passive"))
      (node (ref "U4") (pin "125") (pinfunction "FSMC_NCE4_1/FSMC_NE3/PG10_125") (pintype "passive"))
    )
    (net (code "105") (name "/PG11") (class "Default")
      (node (ref "P12") (pin "12") (pinfunction "12_12") (pintype "passive"))
      (node (ref "U4") (pin "126") (pinfunction "FSMC_NCE4_2/PG11_126") (pintype "passive"))
    )
    (net (code "106") (name "/PG12") (class "Default")
      (node (ref "P12") (pin "11") (pinfunction "11_11") (pintype "passive"))
      (node (ref "U4") (pin "127") (pinfunction "USART6_RTS/FSMC_NE4/PG12_127") (pintype "passive"))
    )
    (net (code "107") (name "/PG13") (class "Default")
      (node (ref "P12") (pin "10") (pinfunction "10_10") (pintype "passive"))
      (node (ref "U4") (pin "128") (pinfunction "USART6_CTS/FSMC_A24/PG13_128") (pintype "passive"))
    )
    (net (code "108") (name "/PG14") (class "Default")
      (node (ref "P12") (pin "9") (pinfunction "9_9") (pintype "passive"))
      (node (ref "U4") (pin "129") (pinfunction "USART6_TX/FSMC_A25/PG14_129") (pintype "passive"))
    )
    (net (code "109") (name "/PG15") (class "Default")
      (node (ref "P12") (pin "8") (pinfunction "8_8") (pintype "passive"))
      (node (ref "U4") (pin "132") (pinfunction "U6_CTS/DCMI_D13/PG15_132") (pintype "passive"))
    )
    (net (code "110") (name "/PH0-OSC_IN") (class "Default")
      (node (ref "C47") (pin "2") (pintype "passive"))
      (node (ref "R24") (pin "1") (pintype "passive"))
      (node (ref "U4") (pin "23") (pinfunction "PHO-OSC_IN_23") (pintype "passive"))
      (node (ref "Y3") (pin "1") (pinfunction "OSC1_1") (pintype "passive"))
    )
    (net (code "111") (name "/PH1-OSC_OUT") (class "Default")
      (node (ref "C48") (pin "2") (pintype "passive"))
      (node (ref "R24") (pin "2") (pintype "passive"))
      (node (ref "U4") (pin "24") (pinfunction "PHI-OSC_OUT_24") (pintype "passive"))
      (node (ref "Y3") (pin "2") (pinfunction "OSC2_2") (pintype "passive"))
    )
    (net (code "112") (name "/RESET") (class "Default")
      (node (ref "C22") (pin "2") (pintype "passive"))
      (node (ref "D3") (pin "1") (pintype "passive"))
      (node (ref "K6") (pin "1") (pinfunction "1_1") (pintype "passive"))
      (node (ref "R11") (pin "1") (pintype "passive"))
      (node (ref "U4") (pin "25") (pinfunction "NRST_25") (pintype "passive"))
    )
    (net (code "113") (name "/RXD") (class "Default")
      (node (ref "P8") (pin "4") (pinfunction "4_4") (pintype "passive"))
      (node (ref "U5") (pin "3") (pinfunction "RXD_3") (pintype "passive"))
    )
    (net (code "114") (name "/TXD") (class "Default")
      (node (ref "P8") (pin "2") (pinfunction "2_2") (pintype "passive"))
      (node (ref "U5") (pin "2") (pinfunction "TXD_2") (pintype "passive"))
    )
    (net (code "115") (name "/VBAT") (class "Default")
      (node (ref "C46") (pin "1") (pintype "passive"))
      (node (ref "D4") (pin "2") (pinfunction "K_2") (pintype "passive"))
      (node (ref "D5") (pin "2") (pinfunction "K_2") (pintype "passive"))
      (node (ref "U4") (pin "6") (pinfunction "VBAT_6") (pintype "passive"))
    )
    (net (code "116") (name "/VDDA") (class "Default")
      (node (ref "C43") (pin "2") (pintype "passive"))
      (node (ref "C44") (pin "2") (pintype "passive"))
      (node (ref "P14") (pin "2") (pinfunction "2_2") (pintype "passive"))
      (node (ref "R20") (pin "1") (pintype "passive"))
      (node (ref "U4") (pin "33") (pinfunction "VDDA_33") (pintype "passive"))
    )
    (net (code "117") (name "/VREF+") (class "Default")
      (node (ref "C45") (pin "2") (pintype "passive"))
      (node (ref "P14") (pin "1") (pinfunction "1_1") (pintype "passive"))
      (node (ref "U4") (pin "32") (pinfunction "Vref+_32") (pintype "passive"))
    )
    (net (code "118") (name "GND") (class "Default")
      (node (ref "2") (pin "2") (pintype "passive"))
      (node (ref "BAT2") (pin "2") (pinfunction "GND_2") (pintype "passive"))
      (node (ref "BOOT2") (pin "5") (pinfunction "5_5") (pintype "passive"))
      (node (ref "BOOT2") (pin "6") (pinfunction "6_6") (pintype "passive"))
      (node (ref "C22") (pin "1") (pintype "passive"))
      (node (ref "C23") (pin "1") (pintype "passive"))
      (node (ref "C24") (pin "1") (pintype "passive"))
      (node (ref "C25") (pin "1") (pintype "passive"))
      (node (ref "C26") (pin "1") (pintype "passive"))
      (node (ref "C27") (pin "1") (pintype "passive"))
      (node (ref "C28") (pin "1") (pintype "passive"))
      (node (ref "C29") (pin "1") (pintype "passive"))
      (node (ref "C30") (pin "1") (pintype "passive"))
      (node (ref "C31") (pin "2") (pinfunction "GND_2") (pintype "passive"))
      (node (ref "C32") (pin "2") (pintype "passive"))
      (node (ref "C33") (pin "1") (pintype "passive"))
      (node (ref "C34") (pin "1") (pintype "passive"))
      (node (ref "C35") (pin "1") (pintype "passive"))
      (node (ref "C36") (pin "1") (pintype "passive"))
      (node (ref "C37") (pin "1") (pintype "passive"))
      (node (ref "C38") (pin "1") (pintype "passive"))
      (node (ref "C39") (pin "1") (pintype "passive"))
      (node (ref "C40") (pin "1") (pintype "passive"))
      (node (ref "C41") (pin "1") (pintype "passive"))
      (node (ref "C42") (pin "1") (pintype "passive"))
      (node (ref "C43") (pin "1") (pintype "passive"))
      (node (ref "C44") (pin "1") (pintype "passive"))
      (node (ref "C45") (pin "1") (pintype "passive"))
      (node (ref "C46") (pin "2") (pintype "passive"))
      (node (ref "C47") (pin "1") (pintype "passive"))
      (node (ref "C48") (pin "1") (pintype "passive"))
      (node (ref "DS6") (pin "2") (pinfunction "K_2") (pintype "passive"))
      (node (ref "K4") (pin "1") (pinfunction "1_1") (pintype "passive"))
      (node (ref "K5") (pin "1") (pinfunction "1_1") (pintype "passive"))
      (node (ref "K6") (pin "2") (pinfunction "2_2") (pintype "passive"))
      (node (ref "P10") (pin "43") (pinfunction "43_43") (pintype "passive"))
      (node (ref "P11") (pin "3") (pinfunction "3_3") (pintype "passive"))
      (node (ref "P12") (pin "44") (pinfunction "44_44") (pintype "passive"))
      (node (ref "R18") (pin "2") (pintype "passive"))
      (node (ref "R20") (pin "2") (pintype "passive"))
      (node (ref "U4") (pin "102") (pinfunction "VSS_102") (pintype "passive"))
      (node (ref "U4") (pin "107") (pinfunction "VSS_107") (pintype "passive"))
      (node (ref "U4") (pin "130") (pinfunction "VSS_130") (pintype "passive"))
      (node (ref "U4") (pin "16") (pinfunction "VSS_16") (pintype "passive"))
      (node (ref "U4") (pin "31") (pinfunction "VSSA_31") (pintype "passive"))
      (node (ref "U4") (pin "38") (pinfunction "VSS_38") (pintype "passive"))
      (node (ref "U4") (pin "51") (pinfunction "VSS_51") (pintype "passive"))
      (node (ref "U4") (pin "61") (pinfunction "VSS_61") (pintype "passive"))
      (node (ref "U4") (pin "83") (pinfunction "VSS_83") (pintype "passive"))
      (node (ref "U4") (pin "94") (pinfunction "VSS_94") (pintype "passive"))
      (node (ref "U5") (pin "1") (pinfunction "GND_1") (pintype "passive"))
      (node (ref "U6") (pin "3") (pinfunction "IN_3") (pintype "passive"))
      (node (ref "USB2") (pin "5") (pinfunction "GND_5") (pintype "passive"))
    )
    (net (code "119") (name "Net-(BAT2-VCC)") (class "Default")
      (node (ref "BAT2") (pin "1") (pinfunction "VCC_1") (pintype "passive"))
      (node (ref "D5") (pin "1") (pinfunction "A_1") (pintype "passive"))
    )
    (net (code "120") (name "Net-(BOOT2-Pad3)") (class "Default")
      (node (ref "BOOT2") (pin "3") (pinfunction "3_3") (pintype "passive"))
      (node (ref "R15") (pin "2") (pintype "passive"))
    )
    (net (code "121") (name "Net-(BOOT2-Pad4)") (class "Default")
      (node (ref "BOOT2") (pin "4") (pinfunction "4_4") (pintype "passive"))
      (node (ref "R16") (pin "1") (pintype "passive"))
    )
    (net (code "122") (name "Net-(DS4-A)") (class "Default")
      (node (ref "DS4") (pin "1") (pinfunction "A_1") (pintype "passive"))
      (node (ref "R21") (pin "1") (pintype "passive"))
    )
    (net (code "123") (name "Net-(DS5-A)") (class "Default")
      (node (ref "DS5") (pin "1") (pinfunction "A_1") (pintype "passive"))
      (node (ref "R22") (pin "1") (pintype "passive"))
    )
    (net (code "124") (name "Net-(DS6-A)") (class "Default")
      (node (ref "DS6") (pin "1") (pinfunction "A_1") (pintype "passive"))
      (node (ref "R23") (pin "1") (pintype "passive"))
    )
    (net (code "125") (name "Net-(Q1-B)") (class "Default")
      (node (ref "Q1") (pin "2") (pinfunction "B_2") (pintype "passive"))
      (node (ref "R13") (pin "1") (pintype "passive"))
    )
    (net (code "126") (name "Net-(Q1-C)") (class "Default")
      (node (ref "D3") (pin "2") (pintype "passive"))
      (node (ref "Q1") (pin "3") (pinfunction "C_3") (pintype "passive"))
      (node (ref "R12") (pin "1") (pintype "passive"))
    )
    (net (code "127") (name "Net-(Q1-E)") (class "Default")
      (node (ref "Q1") (pin "1") (pinfunction "E_1") (pintype "passive"))
      (node (ref "R14") (pin "2") (pintype "passive"))
      (node (ref "U5") (pin "14") (pinfunction "RTS#_14") (pintype "passive"))
    )
    (net (code "128") (name "Net-(Q2-B)") (class "Default")
      (node (ref "Q2") (pin "2") (pinfunction "B_2") (pintype "passive"))
      (node (ref "R14") (pin "1") (pintype "passive"))
    )
    (net (code "129") (name "Net-(Q2-C)") (class "Default")
      (node (ref "Q2") (pin "3") (pinfunction "C_3") (pintype "passive"))
      (node (ref "R17") (pin "2") (pintype "passive"))
    )
    (net (code "130") (name "Net-(U4-PDR_ON)") (class "Default")
      (node (ref "R18") (pin "1") (pintype "passive"))
      (node (ref "R19") (pin "1") (pintype "passive"))
      (node (ref "U4") (pin "143") (pinfunction "PDR_ON_143") (pintype "passive"))
    )
    (net (code "131") (name "Net-(U4-Vcap_1)") (class "Default")
      (node (ref "C32") (pin "1") (pintype "passive"))
      (node (ref "U4") (pin "71") (pinfunction "Vcap_1_71") (pintype "passive"))
    )
    (net (code "132") (name "Net-(U4-Vcap_2)") (class "Default")
      (node (ref "2") (pin "1") (pintype "passive"))
      (node (ref "U4") (pin "106") (pinfunction "Vcap_2_106") (pintype "passive"))
    )
    (net (code "133") (name "Net-(U5-DTR#)") (class "Default")
      (node (ref "R13") (pin "2") (pintype "passive"))
      (node (ref "U5") (pin "13") (pinfunction "DTR#_13") (pintype "passive"))
    )
    (net (code "134") (name "Net-(U5-V3)") (class "Default")
      (node (ref "C25") (pin "2") (pintype "passive"))
      (node (ref "U5") (pin "4") (pinfunction "V3_4") (pintype "passive"))
    )
    (net (code "135") (name "Net-(U5-XI)") (class "Default")
      (node (ref "C27") (pin "2") (pintype "passive"))
      (node (ref "U5") (pin "7") (pinfunction "XI_7") (pintype "passive"))
      (node (ref "Y2") (pin "2") (pinfunction "OSC2_2") (pintype "passive"))
    )
    (net (code "136") (name "Net-(U5-XO)") (class "Default")
      (node (ref "C26") (pin "2") (pintype "passive"))
      (node (ref "U5") (pin "8") (pinfunction "XO_8") (pintype "passive"))
      (node (ref "Y2") (pin "1") (pinfunction "OSC1_1") (pintype "passive"))
    )
    (net (code "137") (name "VCC3.3") (class "Default")
      (node (ref "BOOT2") (pin "1") (pinfunction "1_1") (pintype "passive"))
      (node (ref "BOOT2") (pin "2") (pinfunction "2_2") (pintype "passive"))
      (node (ref "C30") (pin "2") (pintype "passive"))
      (node (ref "C31") (pin "1") (pinfunction "VCC_1") (pintype "passive"))
      (node (ref "C33") (pin "2") (pintype "passive"))
      (node (ref "C34") (pin "2") (pintype "passive"))
      (node (ref "C35") (pin "2") (pintype "passive"))
      (node (ref "C36") (pin "2") (pintype "passive"))
      (node (ref "C37") (pin "2") (pintype "passive"))
      (node (ref "C38") (pin "2") (pintype "passive"))
      (node (ref "C39") (pin "2") (pintype "passive"))
      (node (ref "C40") (pin "2") (pintype "passive"))
      (node (ref "C41") (pin "2") (pintype "passive"))
      (node (ref "C42") (pin "2") (pintype "passive"))
      (node (ref "D4") (pin "1") (pinfunction "A_1") (pintype "passive"))
      (node (ref "P11") (pin "1") (pinfunction "1_1") (pintype "passive"))
      (node (ref "Q2") (pin "1") (pinfunction "E_1") (pintype "passive"))
      (node (ref "R11") (pin "2") (pintype "passive"))
      (node (ref "R12") (pin "2") (pintype "passive"))
      (node (ref "R19") (pin "2") (pintype "passive"))
      (node (ref "R21") (pin "2") (pintype "passive"))
      (node (ref "R22") (pin "2") (pintype "passive"))
      (node (ref "R23") (pin "2") (pintype "passive"))
      (node (ref "U4") (pin "108") (pinfunction "VDD_108") (pintype "passive"))
      (node (ref "U4") (pin "121") (pinfunction "VDD_121") (pintype "passive"))
      (node (ref "U4") (pin "131") (pinfunction "VDD_131") (pintype "passive"))
      (node (ref "U4") (pin "144") (pinfunction "VDD_144") (pintype "passive"))
      (node (ref "U4") (pin "17") (pinfunction "VDD_17") (pintype "passive"))
      (node (ref "U4") (pin "30") (pinfunction "VDD_30") (pintype "passive"))
      (node (ref "U4") (pin "39") (pinfunction "VDD_39") (pintype "passive"))
      (node (ref "U4") (pin "62") (pinfunction "VDD_62") (pintype "passive"))
      (node (ref "U4") (pin "72") (pinfunction "VDD_72") (pintype "passive"))
      (node (ref "U4") (pin "84") (pinfunction "VDD_84") (pintype "passive"))
      (node (ref "U4") (pin "95") (pinfunction "VDD_95") (pintype "passive"))
      (node (ref "U6") (pin "2") (pinfunction "OUT_2") (pintype "passive"))
      (node (ref "U6") (pin "4") (pinfunction "OUT_4") (pintype "passive"))
    )
    (net (code "138") (name "VCC5") (class "Default")
      (node (ref "C23") (pin "2") (pintype "passive"))
      (node (ref "C24") (pin "2") (pintype "passive"))
      (node (ref "C28") (pin "2") (pintype "passive"))
      (node (ref "C29") (pin "2") (pintype "passive"))
      (node (ref "U5") (pin "16") (pinfunction "VCC_16") (pintype "passive"))
      (node (ref "U6") (pin "1") (pinfunction "GND_1") (pintype "passive"))
      (node (ref "USB2") (pin "1") (pinfunction "VCC_1") (pintype "passive"))
    )
    (net (code "139") (name "unconnected-(U4-PB10{slash}SPI2_SCK{slash}I2S2_CK{slash}I2C2_SCL{slash}USART3_TX-Pad69)") (class "Default")
      (node (ref "U4") (pin "69") (pinfunction "PB10/SPI2_SCK/I2S2_CK/I2C2_SCL/USART3_TX_69") (pintype "passive+no_connect"))
    )
    (net (code "140") (name "unconnected-(U4-PB11{slash}I2C2_SDA{slash}USART3_RX-Pad70)") (class "Default")
      (node (ref "U4") (pin "70") (pinfunction "PB11/I2C2_SDA/USART3_RX_70") (pintype "passive+no_connect"))
    )
    (net (code "141") (name "unconnected-(U4-PC14{slash}OSC32_IN-Pad8)") (class "Default")
      (node (ref "U4") (pin "8") (pinfunction "PC14/OSC32_IN_8") (pintype "passive+no_connect"))
    )
    (net (code "142") (name "unconnected-(U4-PC15{slash}OSC32_OUT-Pad9)") (class "Default")
      (node (ref "U4") (pin "9") (pinfunction "PC15/OSC32_OUT_9") (pintype "passive+no_connect"))
    )
    (net (code "143") (name "unconnected-(U5-CTS#-Pad9)") (class "Default")
      (node (ref "U5") (pin "9") (pinfunction "CTS#_9") (pintype "passive"))
    )
    (net (code "144") (name "unconnected-(U5-DCD#-Pad12)") (class "Default")
      (node (ref "U5") (pin "12") (pinfunction "DCD#_12") (pintype "passive"))
    )
    (net (code "145") (name "unconnected-(U5-DSR#-Pad10)") (class "Default")
      (node (ref "U5") (pin "10") (pinfunction "DSR#_10") (pintype "passive"))
    )
    (net (code "146") (name "unconnected-(U5-R232-Pad15)") (class "Default")
      (node (ref "U5") (pin "15") (pinfunction "R232_15") (pintype "passive"))
    )
    (net (code "147") (name "unconnected-(U5-RI#-Pad11)") (class "Default")
      (node (ref "U5") (pin "11") (pinfunction "RI#_11") (pintype "passive"))
    )
    (net (code "148") (name "unconnected-(USB2-NC-Pad4)") (class "Default")
      (node (ref "USB2") (pin "4") (pinfunction "NC_4") (pintype "passive+no_connect"))
    )
  )
)
